# design.net
KiCad netlist of a schematic drawn in Altium Designer
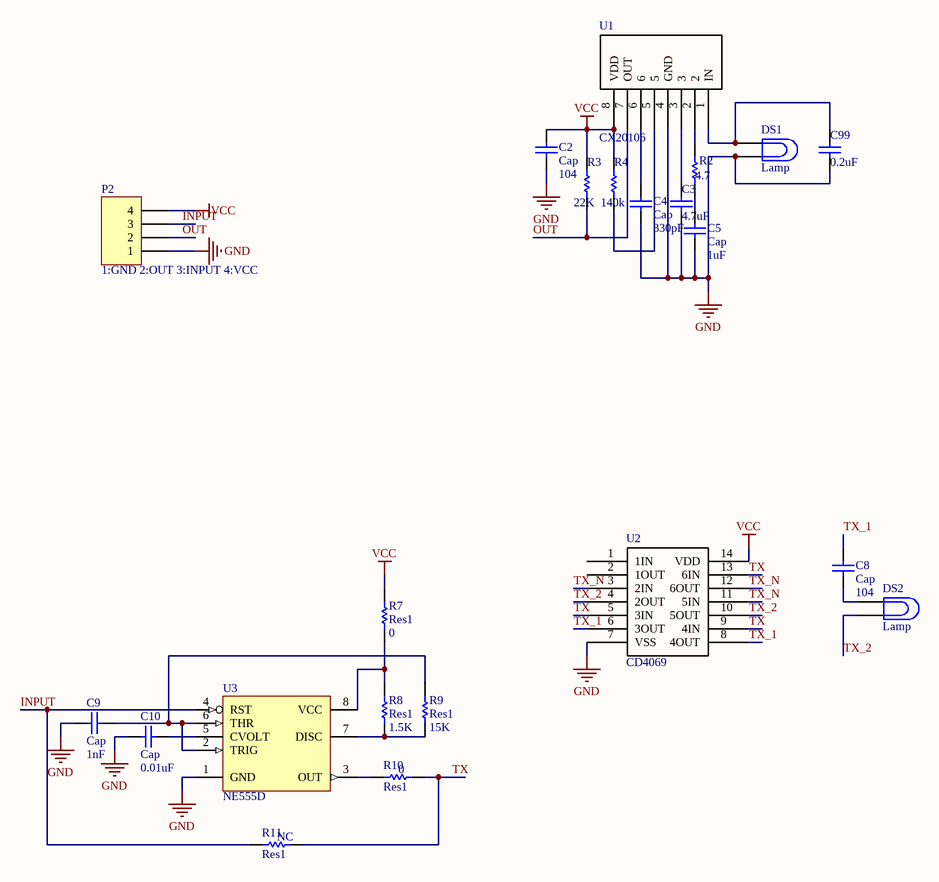
[diagram p0: 超声波.SchDoc]

(export (version "E")
  (design (tool "Eeschema 10.0.6"))
  (components
    (comp (ref "C2")
      (value "Cap")
      (footprint "6-0805")
      (description "Capacitor")
      (fields (field (name "ALTIUM_VALUE") "104") (field (name "PUBLISHER") "Altium Limited"))
      (libsource (lib "Miscellaneous Devices") (part "Cap"))
    )
    (comp (ref "C3")
      (value "4.7uF")
      (footprint "6-0805")
      (description "Capacitor")
      (fields (field (name "PUBLISHER") "Altium Limited"))
      (libsource (lib "Miscellaneous Devices") (part "Cap"))
    )
    (comp (ref "C4")
      (value "Cap")
      (footprint "6-0805")
      (description "Capacitor")
      (fields (field (name "ALTIUM_VALUE") "330pF") (field (name "PUBLISHER") "Altium Limited"))
      (libsource (lib "Miscellaneous Devices") (part "Cap"))
    )
    (comp (ref "C5")
      (value "Cap")
      (footprint "6-0805")
      (description "Capacitor")
      (fields (field (name "ALTIUM_VALUE") "1uF") (field (name "PUBLISHER") "Altium Limited"))
      (libsource (lib "Miscellaneous Devices") (part "Cap"))
    )
    (comp (ref "C8")
      (value "Cap")
      (footprint "6-0805")
      (description "Capacitor")
      (fields (field (name "ALTIUM_VALUE") "104") (field (name "PUBLISHER") "Altium Limited"))
      (libsource (lib "Miscellaneous Devices") (part "Cap"))
    )
    (comp (ref "C9")
      (value "Cap")
      (footprint "6-0805")
      (description "Capacitor")
      (fields (field (name "ALTIUM_VALUE") "1nF") (field (name "PUBLISHER") "Altium Limited"))
      (libsource (lib "Miscellaneous Devices") (part "Cap"))
    )
    (comp (ref "C10")
      (value "Cap")
      (footprint "6-0805")
      (description "Capacitor")
      (fields (field (name "ALTIUM_VALUE") "0.01uF") (field (name "PUBLISHER") "Altium Limited"))
      (libsource (lib "Miscellaneous Devices") (part "Cap"))
    )
    (comp (ref "C99")
      (value "0.2uF")
      (footprint "6-0805")
      (description "Capacitor")
      (fields (field (name "PUBLISHER") "Altium Limited"))
      (libsource (lib "Miscellaneous Devices") (part "Cap"))
    )
    (comp (ref "DS1")
      (value "Lamp")
      (footprint "2pin_10mm")
      (description "Incandescent Bulb")
      (fields (field (name "PUBLISHER") "Altium Limited"))
      (libsource (lib "Miscellaneous Devices") (part "Lamp"))
    )
    (comp (ref "DS2")
      (value "Lamp")
      (footprint "2pin_10mm")
      (description "Incandescent Bulb")
      (fields (field (name "PUBLISHER") "Altium Limited"))
      (libsource (lib "Miscellaneous Devices") (part "Lamp"))
    )
    (comp (ref "P2")
      (value "1:GND 2:OUT 3:INPUT 4:VCC")
      (footprint "HDR1X4")
      (description "Header, 4-Pin")
      (fields (field (name "PUBLISHER") "Altium Limited"))
      (libsource (lib "Miscellaneous Connectors") (part "Header 4"))
    )
    (comp (ref "R2")
      (value "4.7")
      (footprint "2012[0805]")
      (description "Resistor")
      (fields (field (name "PUBLISHER") "Altium Limited"))
      (libsource (lib "Miscellaneous Devices") (part "Res1"))
    )
    (comp (ref "R3")
      (value "22K")
      (footprint "2012[0805]")
      (description "Resistor")
      (fields (field (name "PUBLISHER") "Altium Limited"))
      (libsource (lib "Miscellaneous Devices") (part "Res1"))
    )
    (comp (ref "R4")
      (value "140k")
      (footprint "2012[0805]")
      (description "Resistor")
      (fields (field (name "PUBLISHER") "Altium Limited"))
      (libsource (lib "Miscellaneous Devices") (part "Res1"))
    )
    (comp (ref "R7")
      (value "Res1")
      (footprint "6-0805")
      (description "Resistor")
      (fields (field (name "ALTIUM_VALUE") "0") (field (name "PUBLISHER") "Altium Limited"))
      (libsource (lib "Miscellaneous Devices") (part "Res1"))
    )
    (comp (ref "R8")
      (value "Res1")
      (footprint "6-0805")
      (description "Resistor")
      (fields (field (name "ALTIUM_VALUE") "1.5K") (field (name "PUBLISHER") "Altium Limited"))
      (libsource (lib "Miscellaneous Devices") (part "Res1"))
    )
    (comp (ref "R9")
      (value "Res1")
      (footprint "6-0805")
      (description "Resistor")
      (fields (field (name "ALTIUM_VALUE") "15K") (field (name "PUBLISHER") "Altium Limited"))
      (libsource (lib "Miscellaneous Devices") (part "Res1"))
    )
    (comp (ref "R10")
      (value "Res1")
      (footprint "6-0805")
      (description "Resistor")
      (fields (field (name "ALTIUM_VALUE") "0") (field (name "PUBLISHER") "Altium Limited"))
      (libsource (lib "Miscellaneous Devices") (part "Res1"))
    )
    (comp (ref "R11")
      (value "Res1")
      (footprint "6-0805")
      (description "Resistor")
      (fields (field (name "ALTIUM_VALUE") "NC") (field (name "PUBLISHER") "Altium Limited"))
      (libsource (lib "Miscellaneous Devices") (part "Res1"))
    )
    (comp (ref "U1") (value "CX20106") (footprint "HDR1X8") (libsource (lib "My_SCH_Lib") (part "CX20106")))
    (comp (ref "U2") (value "CD4069") (footprint "SOP-14") (libsource (lib "My_SCH_Lib") (part "CD4069")))
    (comp (ref "U3")
      (value "NE555D")
      (footprint "SO8_N")
      (description "General-Purpose Single Bipolar Timer")
      (fields (field (name "PUBLISHER") "Altium Limited"))
      (libsource (lib "ST Analog Timer Circuit") (part "NE555D"))
    )
  )
  (nets
    (net (code "1") (name "/INPUT") (class "Default")
      (node (ref "P2") (pin "3") (pinfunction "3_3") (pintype "passive"))
      (node (ref "R11") (pin "2") (pinfunction "2_2") (pintype "passive"))
      (node (ref "U3") (pin "4") (pinfunction "RST_4") (pintype "input"))
    )
    (net (code "2") (name "/OUT") (class "Default")
      (node (ref "P2") (pin "2") (pinfunction "2_2") (pintype "passive"))
      (node (ref "R3") (pin "2") (pinfunction "2_2") (pintype "passive"))
      (node (ref "U1") (pin "7") (pinfunction "OUT_7") (pintype "passive"))
    )
    (net (code "3") (name "/TX") (class "Default")
      (node (ref "R10") (pin "1") (pinfunction "1_1") (pintype "passive"))
      (node (ref "R11") (pin "1") (pinfunction "1_1") (pintype "passive"))
      (node (ref "U2") (pin "13") (pinfunction "6IN_13") (pintype "passive"))
      (node (ref "U2") (pin "5") (pinfunction "3IN_5") (pintype "passive"))
      (node (ref "U2") (pin "9") (pinfunction "4IN_9") (pintype "passive"))
    )
    (net (code "4") (name "/TX_1") (class "Default")
      (node (ref "C8") (pin "1") (pinfunction "1_1") (pintype "passive"))
      (node (ref "U2") (pin "6") (pinfunction "3OUT_6") (pintype "passive"))
      (node (ref "U2") (pin "8") (pinfunction "4OUT_8") (pintype "passive"))
    )
    (net (code "5") (name "/TX_2") (class "Default")
      (node (ref "DS2") (pin "2") (pinfunction "2_2") (pintype "passive"))
      (node (ref "U2") (pin "10") (pinfunction "5OUT_10") (pintype "passive"))
      (node (ref "U2") (pin "4") (pinfunction "2OUT_4") (pintype "passive"))
    )
    (net (code "6") (name "/TX_N") (class "Default")
      (node (ref "U2") (pin "11") (pinfunction "5IN_11") (pintype "passive"))
      (node (ref "U2") (pin "12") (pinfunction "6OUT_12") (pintype "passive"))
      (node (ref "U2") (pin "3") (pinfunction "2IN_3") (pintype "passive"))
    )
    (net (code "7") (name "GND") (class "Default")
      (node (ref "C10") (pin "1") (pinfunction "1_1") (pintype "passive"))
      (node (ref "C2") (pin "2") (pinfunction "2_2") (pintype "passive"))
      (node (ref "C3") (pin "2") (pinfunction "2_2") (pintype "passive"))
      (node (ref "C4") (pin "2") (pinfunction "2_2") (pintype "passive"))
      (node (ref "C5") (pin "2") (pinfunction "2_2") (pintype "passive"))
      (node (ref "C9") (pin "1") (pinfunction "1_1") (pintype "passive"))
      (node (ref "C99") (pin "2") (pinfunction "2_2") (pintype "passive"))
      (node (ref "DS1") (pin "2") (pinfunction "2_2") (pintype "passive"))
      (node (ref "P2") (pin "1") (pinfunction "1_1") (pintype "passive"))
      (node (ref "U1") (pin "4") (pinfunction "GND_4") (pintype "passive"))
      (node (ref "U2") (pin "7") (pinfunction "VSS_7") (pintype "passive"))
      (node (ref "U3") (pin "1") (pinfunction "GND_1") (pintype "power_in"))
    )
    (net (code "8") (name "Net-(C3-Pad1)") (class "Default")
      (node (ref "C3") (pin "1") (pinfunction "1_1") (pintype "passive"))
      (node (ref "U1") (pin "3") (pinfunction "3_3") (pintype "passive"))
    )
    (net (code "9") (name "Net-(C4-Pad1)") (class "Default")
      (node (ref "C4") (pin "1") (pinfunction "1_1") (pintype "passive"))
      (node (ref "U1") (pin "6") (pinfunction "6_6") (pintype "passive"))
    )
    (net (code "10") (name "Net-(C5-Pad1)") (class "Default")
      (node (ref "C5") (pin "1") (pinfunction "1_1") (pintype "passive"))
      (node (ref "R2") (pin "2") (pinfunction "2_2") (pintype "passive"))
    )
    (net (code "11") (name "Net-(C8-Pad2)") (class "Default")
      (node (ref "C8") (pin "2") (pinfunction "2_2") (pintype "passive"))
      (node (ref "DS2") (pin "1") (pinfunction "1_1") (pintype "passive"))
    )
    (net (code "12") (name "Net-(R2-Pad1)") (class "Default")
      (node (ref "R2") (pin "1") (pinfunction "1_1") (pintype "passive"))
      (node (ref "U1") (pin "2") (pinfunction "2_2") (pintype "passive"))
    )
    (net (code "13") (name "Net-(R4-Pad2)") (class "Default")
      (node (ref "R4") (pin "2") (pinfunction "2_2") (pintype "passive"))
      (node (ref "U1") (pin "5") (pinfunction "5_5") (pintype "passive"))
    )
    (net (code "14") (name "Net-(U1-IN)") (class "Default")
      (node (ref "C99") (pin "1") (pinfunction "1_1") (pintype "passive"))
      (node (ref "DS1") (pin "1") (pinfunction "1_1") (pintype "passive"))
      (node (ref "U1") (pin "1") (pinfunction "IN_1") (pintype "passive"))
    )
    (net (code "15") (name "Net-(U3-CVOLT)") (class "Default")
      (node (ref "C10") (pin "2") (pinfunction "2_2") (pintype "passive"))
      (node (ref "U3") (pin "5") (pinfunction "CVOLT_5") (pintype "passive"))
    )
    (net (code "16") (name "Net-(U3-DISC)") (class "Default")
      (node (ref "R8") (pin "2") (pinfunction "2_2") (pintype "passive"))
      (node (ref "R9") (pin "2") (pinfunction "2_2") (pintype "passive"))
      (node (ref "U3") (pin "7") (pinfunction "DISC_7") (pintype "open_collector"))
    )
    (net (code "17") (name "Net-(U3-OUT)") (class "Default")
      (node (ref "R10") (pin "2") (pinfunction "2_2") (pintype "passive"))
      (node (ref "U3") (pin "3") (pinfunction "OUT_3") (pintype "output"))
    )
    (net (code "18") (name "Net-(U3-THR)") (class "Default")
      (node (ref "C9") (pin "2") (pinfunction "2_2") (pintype "passive"))
      (node (ref "R9") (pin "1") (pinfunction "1_1") (pintype "passive"))
      (node (ref "U3") (pin "2") (pinfunction "TRIG_2") (pintype "input"))
      (node (ref "U3") (pin "6") (pinfunction "THR_6") (pintype "input"))
    )
    (net (code "19") (name "Net-(U3-VCC)") (class "Default")
      (node (ref "R7") (pin "2") (pinfunction "2_2") (pintype "passive"))
      (node (ref "R8") (pin "1") (pinfunction "1_1") (pintype "passive"))
      (node (ref "U3") (pin "8") (pinfunction "VCC_8") (pintype "power_in"))
    )
    (net (code "20") (name "VCC") (class "Default")
      (node (ref "C2") (pin "1") (pinfunction "1_1") (pintype "passive"))
      (node (ref "P2") (pin "4") (pinfunction "4_4") (pintype "passive"))
      (node (ref "R3") (pin "1") (pinfunction "1_1") (pintype "passive"))
      (node (ref "R4") (pin "1") (pinfunction "1_1") (pintype "passive"))
      (node (ref "R7") (pin "1") (pinfunction "1_1") (pintype "passive"))
      (node (ref "U1") (pin "8") (pinfunction "VDD_8") (pintype "passive"))
      (node (ref "U2") (pin "14") (pinfunction "VDD_14") (pintype "passive"))
    )
    (net (code "21") (name "unconnected-(U2-1IN-Pad1)") (class "Default")
      (node (ref "U2") (pin "1") (pinfunction "1IN_1") (pintype "passive"))
    )
    (net (code "22") (name "unconnected-(U2-1OUT-Pad2)") (class "Default")
      (node (ref "U2") (pin "2") (pinfunction "1OUT_2") (pintype "passive"))
    )
  )
)
